# Driver.net
KiCad netlist of a schematic drawn in Altium Designer
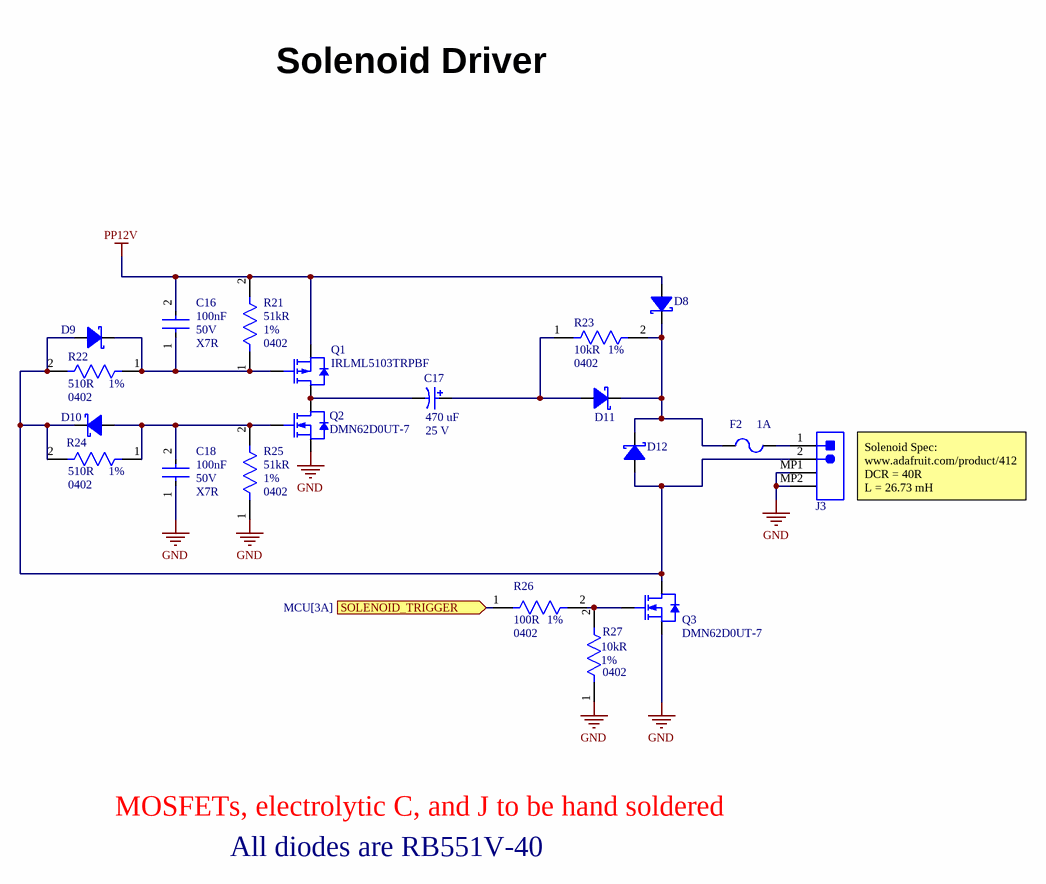
[diagram p0: Driver.SchDoc]

(export (version "E")
  (design (tool "Eeschema 10.0.6"))
  (components
    (comp (ref "C16")
      (value "CL05B104KB54PNC")
      (footprint "CAP0402")
      (description "50V 100nF X7R ±10% 0402  Multilayer Ceramic Capacitors MLCC - SMD/SMT ROHS")
      (fields
        (field (name "TOLERANCE") "±20%")
        (field (name "MANUFACTURER") "Samsung Electro-Mechanics")
        (field (name "DIELECTRIC") "X7R")
        (field (name "VOLTAGE RATING") "50V")
        (field (name "CAPACITANCE") "100nF")
      )
      (libsource (lib "FYDP_library_sch") (part "CAP0402"))
    )
    (comp (ref "C17")
      (value "UUD1E471MNL1GS")
      (footprint "NIC-CAPA2-10X10_V")
      (fields
        (field (name "RATED CAPACITANCE") "470 uF")
        (field (name "MANUFACTURER") "Nichicon")
        (field (name "RATED VOLTAGE") "25 V")
      )
      (libsource (lib "Altium Content Vault") (part "NIC-CAP-P-2"))
    )
    (comp (ref "C18")
      (value "CL05B104KB54PNC")
      (footprint "CAP0402")
      (description "50V 100nF X7R ±10% 0402  Multilayer Ceramic Capacitors MLCC - SMD/SMT ROHS")
      (fields
        (field (name "TOLERANCE") "±20%")
        (field (name "MANUFACTURER") "Samsung Electro-Mechanics")
        (field (name "DIELECTRIC") "X7R")
        (field (name "VOLTAGE RATING") "50V")
        (field (name "CAPACITANCE") "100nF")
      )
      (libsource (lib "FYDP_library_sch") (part "CAP0402"))
    )
    (comp (ref "D8")
      (value "RB551V-40")
      (footprint "SOD-323")
      (description "40V 470mV@500mA 0.5A SOD-323  Schottky Barrier Diodes (SBD) ROHS")
      (fields (field (name "MANUFACTURER") "Taiwan Semiconductor"))
      (libsource (lib "FYDP_library_sch") (part "RB551V-40"))
    )
    (comp (ref "D9")
      (value "RB551V-40")
      (footprint "SOD-323")
      (description "40V 470mV@500mA 0.5A SOD-323  Schottky Barrier Diodes (SBD) ROHS")
      (fields (field (name "MANUFACTURER") "Taiwan Semiconductor"))
      (libsource (lib "FYDP_library_sch") (part "RB551V-40"))
    )
    (comp (ref "D10")
      (value "RB551V-40")
      (footprint "SOD-323")
      (description "40V 470mV@500mA 0.5A SOD-323  Schottky Barrier Diodes (SBD) ROHS")
      (fields (field (name "MANUFACTURER") "Taiwan Semiconductor"))
      (libsource (lib "FYDP_library_sch") (part "RB551V-40"))
    )
    (comp (ref "D11")
      (value "RB551V-40")
      (footprint "SOD-323")
      (description "40V 470mV@500mA 0.5A SOD-323  Schottky Barrier Diodes (SBD) ROHS")
      (fields (field (name "MANUFACTURER") "Taiwan Semiconductor"))
      (libsource (lib "FYDP_library_sch") (part "RB551V-40"))
    )
    (comp (ref "D12")
      (value "RB551V-40")
      (footprint "SOD-323")
      (description "40V 470mV@500mA 0.5A SOD-323  Schottky Barrier Diodes (SBD) ROHS")
      (fields (field (name "MANUFACTURER") "Taiwan Semiconductor"))
      (libsource (lib "FYDP_library_sch") (part "RB551V-40"))
    )
    (comp (ref "F2")
      (value "0467001.NRHF")
      (footprint "FUSE_0603")
      (description "50A SMD Fuse 1A 32V 32V 0603  Fuses ROHS")
      (fields (field (name "MANUFACTURER") "Littelfuse") (field (name "CURRENT RATING") "1A"))
      (libsource (lib "FYDP_library_sch") (part "FUSE0603"))
    )
    (comp (ref "J3")
      (value "S2B-PH-SM4-TB(LF)(SN)")
      (footprint "JST- S2B-PH-SM4-TB(LF)(SN)-2_V")
      (description "Male Header, Pitch 2 mm, 1 x 2 Position, Height 5.5 mm, -25 to 85 degC, RoHS, Tape and Reel")
      (libsource (lib "Altium Content Vault") (part "CN-1P-2M-R2"))
    )
    (comp (ref "Q1")
      (value "IRLML5103TRPBF")
      (footprint "SOT23-3")
      (description "P-Channel 30 V 760mA (Ta) 540mW (Ta) Surface Mount Micro3™/SOT-23")
      (libsource (lib "FYDP_library_sch") (part "IRLML5103TRPBF"))
    )
    (comp (ref "Q2")
      (value "DMN62D0UT-7")
      (footprint "SOT-523")
      (description "NFET 60 V 320mA (Ta) 230mW (Ta) Surface Mount SOT-523")
      (libsource (lib "FYDP_library_sch") (part "DMN62D0UT-7"))
    )
    (comp (ref "Q3")
      (value "DMN62D0UT-7")
      (footprint "SOT-523")
      (description "NFET 60 V 320mA (Ta) 230mW (Ta) Surface Mount SOT-523")
      (libsource (lib "FYDP_library_sch") (part "DMN62D0UT-7"))
    )
    (comp (ref "R21")
      (value "0402WGF5102TCE")
      (footprint "RES0402")
      (description "62.5mW Thick Film Resistors ±100ppm/℃ ±1% 51kΩ 0402  Chip Resistor - Surface Mount ROHS")
      (fields
        (field (name "MANUFACTURER") "UNI-ROYAL(Uniroyal Elec)")
        (field (name "TOLERANCE") "1%")
        (field (name "RESISTANCE") "51kR")
        (field (name "PACKAGE") "0402")
      )
      (libsource (lib "FYDP_library_sch") (part "RES0402"))
    )
    (comp (ref "R22")
      (value "0402WGF5100TCE")
      (footprint "RES0402")
      (description "62.5mW Thick Film Resistors ±100ppm/℃ ±1% 510Ω 0402  Chip Resistor - Surface Mount ROHS")
      (fields
        (field (name "MANUFACTURER") "UNI-ROYAL(Uniroyal Elec)")
        (field (name "TOLERANCE") "1%")
        (field (name "RESISTANCE") "510R")
        (field (name "PACKAGE") "0402")
      )
      (libsource (lib "FYDP_library_sch") (part "RES0402"))
    )
    (comp (ref "R23")
      (value "0402WGF1002TCE")
      (footprint "RES0402")
      (description "62.5mW Thick Film Resistors ±100ppm/℃ ±1% 10kΩ 0402  Chip Resistor - Surface Mount ROHS")
      (fields
        (field (name "MANUFACTURER") "UNI-ROYAL(Uniroyal Elec)")
        (field (name "TOLERANCE") "1%")
        (field (name "RESISTANCE") "10kR")
        (field (name "PACKAGE") "0402")
      )
      (libsource (lib "FYDP_library_sch") (part "RES0402"))
    )
    (comp (ref "R24")
      (value "0402WGF5100TCE")
      (footprint "RES0402")
      (description "62.5mW Thick Film Resistors ±100ppm/℃ ±1% 510Ω 0402  Chip Resistor - Surface Mount ROHS")
      (fields
        (field (name "MANUFACTURER") "UNI-ROYAL(Uniroyal Elec)")
        (field (name "TOLERANCE") "1%")
        (field (name "RESISTANCE") "510R")
        (field (name "PACKAGE") "0402")
      )
      (libsource (lib "FYDP_library_sch") (part "RES0402"))
    )
    (comp (ref "R25")
      (value "0402WGF5102TCE")
      (footprint "RES0402")
      (description "62.5mW Thick Film Resistors ±100ppm/℃ ±1% 51kΩ 0402  Chip Resistor - Surface Mount ROHS")
      (fields
        (field (name "MANUFACTURER") "UNI-ROYAL(Uniroyal Elec)")
        (field (name "TOLERANCE") "1%")
        (field (name "RESISTANCE") "51kR")
        (field (name "PACKAGE") "0402")
      )
      (libsource (lib "FYDP_library_sch") (part "RES0402"))
    )
    (comp (ref "R26")
      (value "0402WGF1000TCE")
      (footprint "RES0402")
      (description "62.5mW Thick Film Resistors ±1% ±200ppm/℃ 100Ω 0402  Chip Resistor - Surface Mount ROHS")
      (fields
        (field (name "MANUFACTURER") "UNI-ROYAL(Uniroyal Elec)")
        (field (name "TOLERANCE") "1%")
        (field (name "RESISTANCE") "100R")
        (field (name "PACKAGE") "0402")
      )
      (libsource (lib "FYDP_library_sch") (part "RES0402"))
    )
    (comp (ref "R27")
      (value "0402WGF1002TCE")
      (footprint "RES0402")
      (description "62.5mW Thick Film Resistors ±100ppm/℃ ±1% 10kΩ 0402  Chip Resistor - Surface Mount ROHS")
      (fields
        (field (name "MANUFACTURER") "UNI-ROYAL(Uniroyal Elec)")
        (field (name "TOLERANCE") "1%")
        (field (name "RESISTANCE") "10kR")
        (field (name "PACKAGE") "0402")
      )
      (libsource (lib "FYDP_library_sch") (part "RES0402"))
    )
  )
  (nets
    (net (code "1") (name "/SOLENOID_TRIGGER") (class "Default")
      (node (ref "R26") (pin "1") (pinfunction "1_1") (pintype "passive"))
    )
    (net (code "2") (name "GND") (class "Default")
      (node (ref "C18") (pin "1") (pinfunction "1_1") (pintype "passive"))
      (node (ref "J3") (pin "MP1") (pinfunction "MP1_MP1") (pintype "passive"))
      (node (ref "J3") (pin "MP2") (pinfunction "MP2_MP2") (pintype "passive"))
      (node (ref "Q2") (pin "2") (pinfunction "SOURCE_2") (pintype "passive"))
      (node (ref "Q3") (pin "2") (pinfunction "SOURCE_2") (pintype "passive"))
      (node (ref "R25") (pin "1") (pinfunction "1_1") (pintype "passive"))
      (node (ref "R27") (pin "1") (pinfunction "1_1") (pintype "passive"))
    )
    (net (code "3") (name "Net-(D9-Cathode)") (class "Default")
      (node (ref "C16") (pin "1") (pinfunction "1_1") (pintype "passive"))
      (node (ref "D9") (pin "1") (pinfunction "Cathode_1") (pintype "passive"))
      (node (ref "Q1") (pin "1") (pinfunction "Gate_1") (pintype "passive"))
      (node (ref "R21") (pin "1") (pinfunction "1_1") (pintype "passive"))
      (node (ref "R22") (pin "1") (pinfunction "1_1") (pintype "passive"))
    )
    (net (code "4") (name "Net-(D10-Anode)") (class "Default")
      (node (ref "C18") (pin "2") (pinfunction "2_2") (pintype "passive"))
      (node (ref "D10") (pin "2") (pinfunction "Anode_2") (pintype "passive"))
      (node (ref "Q2") (pin "1") (pinfunction "GATE_1") (pintype "passive"))
      (node (ref "R24") (pin "1") (pinfunction "1_1") (pintype "passive"))
      (node (ref "R25") (pin "2") (pinfunction "2_2") (pintype "passive"))
    )
    (net (code "5") (name "Net-(D10-Cathode)") (class "Default")
      (node (ref "D10") (pin "1") (pinfunction "Cathode_1") (pintype "passive"))
      (node (ref "D12") (pin "2") (pinfunction "Anode_2") (pintype "passive"))
      (node (ref "D9") (pin "2") (pinfunction "Anode_2") (pintype "passive"))
      (node (ref "J3") (pin "2") (pinfunction "2_2") (pintype "passive"))
      (node (ref "Q3") (pin "3") (pinfunction "DRAIN_3") (pintype "passive"))
      (node (ref "R22") (pin "2") (pinfunction "2_2") (pintype "passive"))
      (node (ref "R24") (pin "2") (pinfunction "2_2") (pintype "passive"))
    )
    (net (code "6") (name "Net-(D11-Anode)") (class "Default")
      (node (ref "C17") (pin "1") (pinfunction "1_1") (pintype "passive"))
      (node (ref "D11") (pin "2") (pinfunction "Anode_2") (pintype "passive"))
      (node (ref "R23") (pin "1") (pinfunction "1_1") (pintype "passive"))
    )
    (net (code "7") (name "Net-(D11-Cathode)") (class "Default")
      (node (ref "D11") (pin "1") (pinfunction "Cathode_1") (pintype "passive"))
      (node (ref "D12") (pin "1") (pinfunction "Cathode_1") (pintype "passive"))
      (node (ref "D8") (pin "1") (pinfunction "Cathode_1") (pintype "passive"))
      (node (ref "F2") (pin "1") (pinfunction "1_1") (pintype "passive"))
      (node (ref "R23") (pin "2") (pinfunction "2_2") (pintype "passive"))
    )
    (net (code "8") (name "Net-(F2-Pad2)") (class "Default")
      (node (ref "F2") (pin "2") (pinfunction "2_2") (pintype "passive"))
      (node (ref "J3") (pin "1") (pinfunction "1_1") (pintype "passive"))
    )
    (net (code "9") (name "Net-(Q1-Drain)") (class "Default")
      (node (ref "C17") (pin "2") (pinfunction "2_2") (pintype "passive"))
      (node (ref "Q1") (pin "3") (pinfunction "Drain_3") (pintype "passive"))
      (node (ref "Q2") (pin "3") (pinfunction "DRAIN_3") (pintype "passive"))
    )
    (net (code "10") (name "Net-(Q3-GATE)") (class "Default")
      (node (ref "Q3") (pin "1") (pinfunction "GATE_1") (pintype "passive"))
      (node (ref "R26") (pin "2") (pinfunction "2_2") (pintype "passive"))
      (node (ref "R27") (pin "2") (pinfunction "2_2") (pintype "passive"))
    )
    (net (code "11") (name "PP12V") (class "Default")
      (node (ref "C16") (pin "2") (pinfunction "2_2") (pintype "passive"))
      (node (ref "D8") (pin "2") (pinfunction "Anode_2") (pintype "passive"))
      (node (ref "Q1") (pin "2") (pinfunction "Source_2") (pintype "passive"))
      (node (ref "R21") (pin "2") (pinfunction "2_2") (pintype "passive"))
    )
  )
)
